# arduinoSerialProg.net
KiCad netlist of a schematic drawn in EAGLE
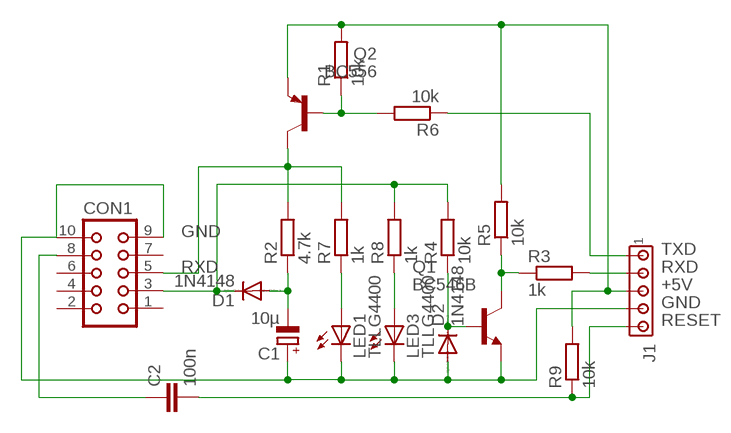
[diagram p0: schematic, sheet 1]

(export (version "E")
  (design (tool "Eeschema 10.0.6"))
  (components
    (comp (ref "C1")
      (value "10µ")
      (footprint "eagle-import:E2,5-6E")
      (libsource (lib "eagle-import") (part "CPOL-EUE2,5-6E"))
    )
    (comp (ref "C2")
      (value "100n")
      (footprint "eagle-import:C050-025X075")
      (libsource (lib "eagle-import") (part "C-EU050-025X075"))
    )
    (comp (ref "CON1")
      (value "CON10")
      (footprint "eagle-import:CON10")
      (libsource (lib "eagle-import") (part "CON10"))
    )
    (comp (ref "D1")
      (value "1N4148")
      (footprint "eagle-import:DO35-10")
      (libsource (lib "eagle-import") (part "1N4148DO35-10"))
    )
    (comp (ref "D2")
      (value "1N4148")
      (footprint "eagle-import:DO35-10")
      (libsource (lib "eagle-import") (part "1N4148DO35-10"))
    )
    (comp (ref "J1")
      (value "MTA05-100")
      (footprint "eagle-import:10X05MTA")
      (libsource (lib "eagle-import") (part "MTA05-100"))
    )
    (comp (ref "LED1")
      (value "TLLG4400")
      (footprint "eagle-import:LED3MM")
      (fields (field (name "MF") "VISHAY SEMICONDUCTOR"))
      (libsource (lib "eagle-import") (part "TLLG4400"))
    )
    (comp (ref "LED3")
      (value "TLLG4400")
      (footprint "eagle-import:LED3MM")
      (fields (field (name "MF") "VISHAY SEMICONDUCTOR"))
      (libsource (lib "eagle-import") (part "TLLG4400"))
    )
    (comp (ref "Q1")
      (value "BC546B")
      (footprint "eagle-import:TO92-EBC")
      (libsource (lib "eagle-import") (part "BC546B"))
    )
    (comp (ref "Q2")
      (value "BC556")
      (footprint "eagle-import:TO92-EBC")
      (libsource (lib "eagle-import") (part "BC556"))
    )
    (comp (ref "R1")
      (value "10k")
      (footprint "eagle-import:0204V")
      (libsource (lib "eagle-import") (part "R-EU_0204/2V"))
    )
    (comp (ref "R2")
      (value "4.7k")
      (footprint "eagle-import:0207_10")
      (libsource (lib "eagle-import") (part "R-EU_0207/10"))
    )
    (comp (ref "R3")
      (value "1k")
      (footprint "eagle-import:0207_10")
      (libsource (lib "eagle-import") (part "R-EU_0207/10"))
    )
    (comp (ref "R4")
      (value "10k")
      (footprint "eagle-import:0207_10")
      (libsource (lib "eagle-import") (part "R-EU_0207/10"))
    )
    (comp (ref "R5")
      (value "10k")
      (footprint "eagle-import:0204V")
      (libsource (lib "eagle-import") (part "R-EU_0204/2V"))
    )
    (comp (ref "R6")
      (value "10k")
      (footprint "eagle-import:0207_10")
      (libsource (lib "eagle-import") (part "R-EU_0207/10"))
    )
    (comp (ref "R7")
      (value "1k")
      (footprint "eagle-import:0207_10")
      (libsource (lib "eagle-import") (part "R-EU_0207/10"))
    )
    (comp (ref "R8")
      (value "1k")
      (footprint "eagle-import:0207_10")
      (libsource (lib "eagle-import") (part "R-EU_0207/10"))
    )
    (comp (ref "R9")
      (value "10k")
      (footprint "eagle-import:0207_10")
      (libsource (lib "eagle-import") (part "R-EU_0207/10"))
    )
  )
  (nets
    (net (code "1") (name "/+5V") (class "Default")
      (node (ref "J1") (pin "3") (pinfunction "3_3") (pintype "passive"))
      (node (ref "Q2") (pin "E") (pinfunction "E_E") (pintype "passive"))
      (node (ref "R1") (pin "2") (pinfunction "2_2") (pintype "passive"))
      (node (ref "R5") (pin "2") (pinfunction "2_2") (pintype "passive"))
      (node (ref "R9") (pin "2") (pinfunction "2_2") (pintype "passive"))
    )
    (net (code "2") (name "/GND") (class "Default")
      (node (ref "C1") (pin "+") (pinfunction "+_+") (pintype "passive"))
      (node (ref "CON1") (pin "10") (pinfunction "10_10") (pintype "passive"))
      (node (ref "CON1") (pin "9") (pinfunction "9_9") (pintype "passive"))
      (node (ref "D2") (pin "A") (pinfunction "A_A") (pintype "passive"))
      (node (ref "J1") (pin "4") (pinfunction "4_4") (pintype "passive"))
      (node (ref "LED1") (pin "K") (pinfunction "C_K") (pintype "passive"))
      (node (ref "LED3") (pin "K") (pinfunction "C_K") (pintype "passive"))
      (node (ref "Q1") (pin "E") (pinfunction "E_E") (pintype "passive"))
    )
    (net (code "3") (name "/RESET") (class "Default")
      (node (ref "C2") (pin "2") (pinfunction "2_2") (pintype "passive"))
      (node (ref "J1") (pin "5") (pinfunction "5_5") (pintype "passive"))
      (node (ref "R9") (pin "1") (pinfunction "1_1") (pintype "passive"))
    )
    (net (code "4") (name "/RXD") (class "Default")
      (node (ref "CON1") (pin "5") (pinfunction "5_5") (pintype "passive"))
      (node (ref "J1") (pin "2") (pinfunction "2_2") (pintype "passive"))
      (node (ref "Q2") (pin "C") (pinfunction "C_C") (pintype "passive"))
      (node (ref "R2") (pin "2") (pinfunction "2_2") (pintype "passive"))
      (node (ref "R3") (pin "2") (pinfunction "2_2") (pintype "passive"))
      (node (ref "R7") (pin "2") (pinfunction "2_2") (pintype "passive"))
    )
    (net (code "5") (name "/TXD") (class "Default")
      (node (ref "CON1") (pin "3") (pinfunction "3_3") (pintype "passive"))
      (node (ref "D1") (pin "C") (pinfunction "C_C") (pintype "passive"))
      (node (ref "J1") (pin "1") (pinfunction "1_1") (pintype "passive"))
      (node (ref "R4") (pin "2") (pinfunction "2_2") (pintype "passive"))
      (node (ref "R6") (pin "1") (pinfunction "1_1") (pintype "passive"))
      (node (ref "R8") (pin "2") (pinfunction "2_2") (pintype "passive"))
    )
    (net (code "6") (name "Net-(C1-Pad-)") (class "Default")
      (node (ref "C1") (pin "-") (pinfunction "-_-") (pintype "passive"))
      (node (ref "D1") (pin "A") (pinfunction "A_A") (pintype "passive"))
      (node (ref "R2") (pin "1") (pinfunction "1_1") (pintype "passive"))
    )
    (net (code "7") (name "Net-(C2-Pad1)") (class "Default")
      (node (ref "C2") (pin "1") (pinfunction "1_1") (pintype "passive"))
      (node (ref "CON1") (pin "8") (pinfunction "8_8") (pintype "passive"))
    )
    (net (code "8") (name "Net-(D2-PadC)") (class "Default")
      (node (ref "D2") (pin "C") (pinfunction "C_C") (pintype "passive"))
      (node (ref "Q1") (pin "B") (pinfunction "B_B") (pintype "passive"))
      (node (ref "R4") (pin "1") (pinfunction "1_1") (pintype "passive"))
    )
    (net (code "9") (name "Net-(LED1-PadA)") (class "Default")
      (node (ref "LED1") (pin "A") (pinfunction "A_A") (pintype "passive"))
      (node (ref "R7") (pin "1") (pinfunction "1_1") (pintype "passive"))
    )
    (net (code "10") (name "Net-(LED3-PadA)") (class "Default")
      (node (ref "LED3") (pin "A") (pinfunction "A_A") (pintype "passive"))
      (node (ref "R8") (pin "1") (pinfunction "1_1") (pintype "passive"))
    )
    (net (code "11") (name "Net-(Q1-PadC)") (class "Default")
      (node (ref "Q1") (pin "C") (pinfunction "C_C") (pintype "passive"))
      (node (ref "R3") (pin "1") (pinfunction "1_1") (pintype "passive"))
      (node (ref "R5") (pin "1") (pinfunction "1_1") (pintype "passive"))
    )
    (net (code "12") (name "Net-(Q2-PadB)") (class "Default")
      (node (ref "Q2") (pin "B") (pinfunction "B_B") (pintype "passive"))
      (node (ref "R1") (pin "1") (pinfunction "1_1") (pintype "passive"))
      (node (ref "R6") (pin "2") (pinfunction "2_2") (pintype "passive"))
    )
    (net (code "13") (name "unconnected-(CON1-Pad1)") (class "Default")
      (node (ref "CON1") (pin "1") (pinfunction "1_1") (pintype "passive"))
    )
    (net (code "14") (name "unconnected-(CON1-Pad2)") (class "Default")
      (node (ref "CON1") (pin "2") (pinfunction "2_2") (pintype "passive"))
    )
    (net (code "15") (name "unconnected-(CON1-Pad4)") (class "Default")
      (node (ref "CON1") (pin "4") (pinfunction "4_4") (pintype "passive"))
    )
    (net (code "16") (name "unconnected-(CON1-Pad6)") (class "Default")
      (node (ref "CON1") (pin "6") (pinfunction "6_6") (pintype "passive"))
    )
    (net (code "17") (name "unconnected-(CON1-Pad7)") (class "Default")
      (node (ref "CON1") (pin "7") (pinfunction "7_7") (pintype "passive"))
    )
  )
)
